# network.net
KiCad netlist of a schematic drawn in Altium Designer
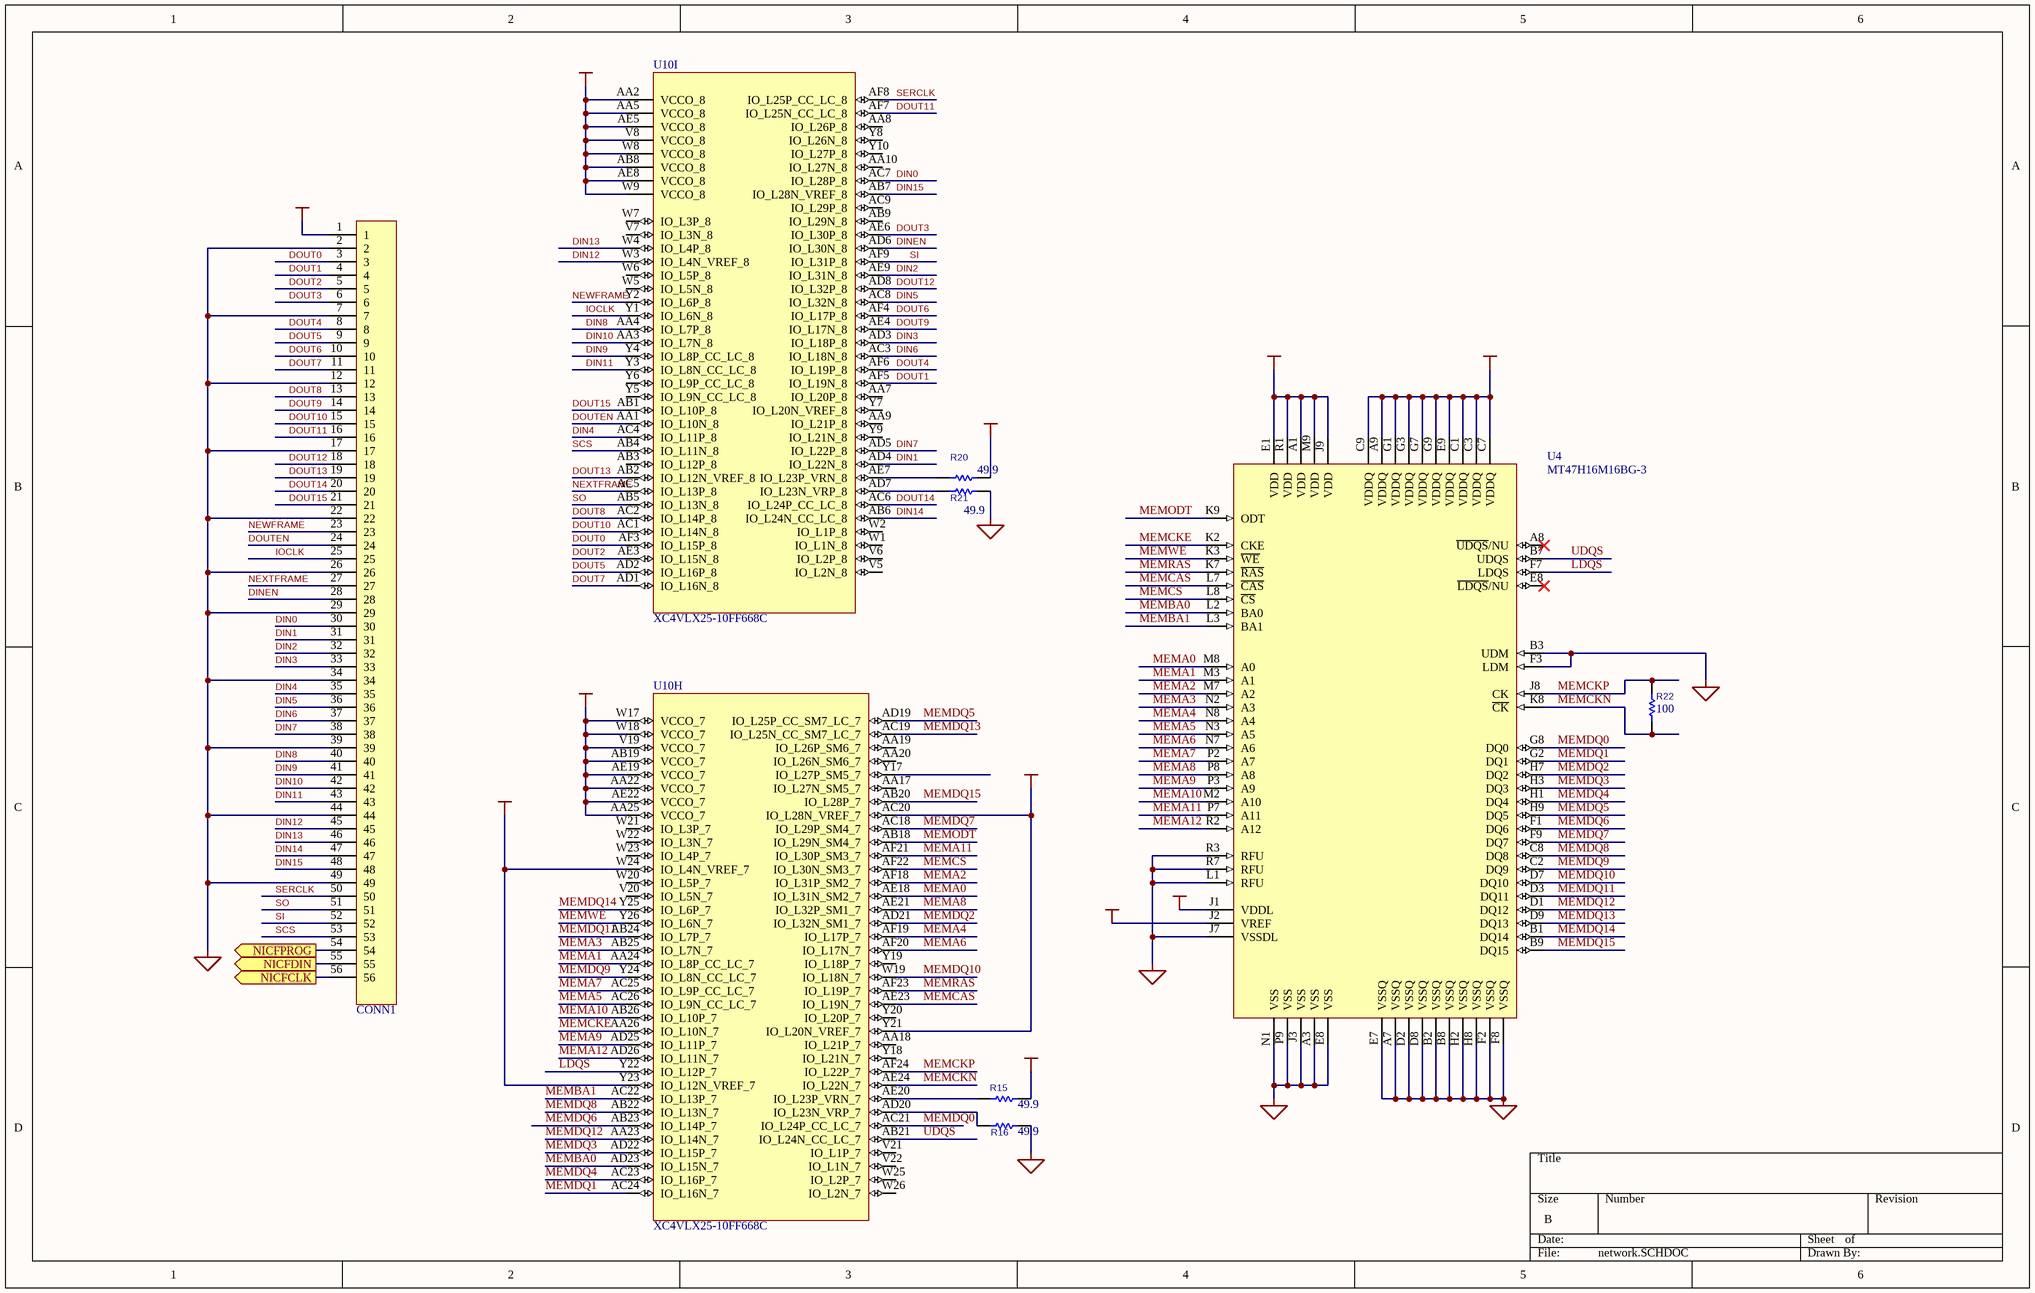
[diagram p0: network.SCHDOC]

(export (version "E")
  (design (tool "Eeschema 10.0.6"))
  (components
    (comp (ref "CONN1") (value "CON56B") (footprint "HDR56") (libsource (lib "parts") (part "CON56B")))
    (comp (ref "R15")
      (value "49.9")
      (footprint "0402")
      (description "Standard Passive Resistor")
      (fields (field (name "TOLERANCE") "1%") (field (name "Comment") "50"))
      (libsource (lib "parts") (part "RESISTOR"))
    )
    (comp (ref "R16")
      (value "49.9")
      (footprint "0402")
      (description "Standard Passive Resistor")
      (fields (field (name "TOLERANCE") "1%") (field (name "Comment") "50"))
      (libsource (lib "parts") (part "RESISTOR"))
    )
    (comp (ref "R20")
      (value "49.9")
      (footprint "0402")
      (description "Standard Passive Resistor")
      (fields (field (name "TOLERANCE") "1%") (field (name "Comment") "50"))
      (libsource (lib "parts") (part "RESISTOR"))
    )
    (comp (ref "R21")
      (value "49.9")
      (footprint "0402")
      (description "Standard Passive Resistor")
      (fields (field (name "TOLERANCE") "1%") (field (name "Comment") "50"))
      (libsource (lib "parts") (part "RESISTOR"))
    )
    (comp (ref "R22")
      (value "100")
      (footprint "0402")
      (description "Standard Passive Resistor")
      (fields (field (name "TOLERANCE") "1%") (field (name "Comment") "50"))
      (libsource (lib "parts") (part "RESISTOR"))
    )
    (comp (ref "U4")
      (value "MT47H16M16BG-3")
      (footprint "MICRON84FBGA")
      (description "Micron DDR2 SDRAM")
      (libsource (lib "parts") (part "MT47H16M16BG-3"))
    )
    (comp (ref "U10")
      (value "XC4VLX25-10FF668C")
      (footprint "Xilinx FF668")
      (description "Xilinx Virtex-4")
      (libsource (lib "parts") (part "XC4VLX25-10FF668C"))
    )
  )
  (nets
    (net (code "1") (name "+0.9VCC") (class "Default")
      (node (ref "U10") (pin "AC20") (pinfunction "IO_L28N_VREF_7_AC20") (pintype "bidirectional"))
      (node (ref "U10") (pin "W24") (pinfunction "IO_L4N_VREF_7_W24") (pintype "bidirectional"))
      (node (ref "U10") (pin "Y21") (pinfunction "IO_L20N_VREF_7_Y21") (pintype "bidirectional"))
      (node (ref "U10") (pin "Y23") (pinfunction "IO_L12N_VREF_7_Y23") (pintype "bidirectional"))
      (node (ref "U4") (pin "J2") (pinfunction "VREF_J2") (pintype "power_in"))
    )
    (net (code "2") (name "+1.8VCC") (class "Default")
      (node (ref "R15") (pin "1") (pintype "passive"))
      (node (ref "U10") (pin "AA22") (pinfunction "VCCO_7_AA22") (pintype "bidirectional"))
      (node (ref "U10") (pin "AA25") (pinfunction "VCCO_7_AA25") (pintype "bidirectional"))
      (node (ref "U10") (pin "AB19") (pinfunction "VCCO_7_AB19") (pintype "bidirectional"))
      (node (ref "U10") (pin "AE19") (pinfunction "VCCO_7_AE19") (pintype "bidirectional"))
      (node (ref "U10") (pin "AE22") (pinfunction "VCCO_7_AE22") (pintype "bidirectional"))
      (node (ref "U10") (pin "V19") (pinfunction "VCCO_7_V19") (pintype "bidirectional"))
      (node (ref "U10") (pin "W17") (pinfunction "VCCO_7_W17") (pintype "bidirectional"))
      (node (ref "U10") (pin "W18") (pinfunction "VCCO_7_W18") (pintype "bidirectional"))
      (node (ref "U4") (pin "A1") (pinfunction "VDD_A1") (pintype "power_in"))
      (node (ref "U4") (pin "A9") (pinfunction "VDDQ_A9") (pintype "power_in"))
      (node (ref "U4") (pin "C1") (pinfunction "VDDQ_C1") (pintype "power_in"))
      (node (ref "U4") (pin "C3") (pinfunction "VDDQ_C3") (pintype "power_in"))
      (node (ref "U4") (pin "C7") (pinfunction "VDDQ_C7") (pintype "power_in"))
      (node (ref "U4") (pin "C9") (pinfunction "VDDQ_C9") (pintype "power_in"))
      (node (ref "U4") (pin "E1") (pinfunction "VDD_E1") (pintype "power_in"))
      (node (ref "U4") (pin "E9") (pinfunction "VDDQ_E9") (pintype "power_in"))
      (node (ref "U4") (pin "G1") (pinfunction "VDDQ_G1") (pintype "power_in"))
      (node (ref "U4") (pin "G3") (pinfunction "VDDQ_G3") (pintype "power_in"))
      (node (ref "U4") (pin "G7") (pinfunction "VDDQ_G7") (pintype "power_in"))
      (node (ref "U4") (pin "G9") (pinfunction "VDDQ_G9") (pintype "power_in"))
      (node (ref "U4") (pin "J1") (pinfunction "VDDL_J1") (pintype "power_in"))
      (node (ref "U4") (pin "J9") (pinfunction "VDD_J9") (pintype "power_in"))
      (node (ref "U4") (pin "M9") (pinfunction "VDD_M9") (pintype "power_in"))
      (node (ref "U4") (pin "R1") (pinfunction "VDD_R1") (pintype "power_in"))
    )
    (net (code "3") (name "/DIN0") (class "Default")
      (node (ref "CONN1") (pin "30") (pinfunction "30_30") (pintype "passive"))
      (node (ref "U10") (pin "AC7") (pinfunction "IO_L28P_8_AC7") (pintype "bidirectional"))
    )
    (net (code "4") (name "/DIN1") (class "Default")
      (node (ref "CONN1") (pin "31") (pinfunction "31_31") (pintype "passive"))
      (node (ref "U10") (pin "AD4") (pinfunction "IO_L22N_8_AD4") (pintype "bidirectional"))
    )
    (net (code "5") (name "/DIN2") (class "Default")
      (node (ref "CONN1") (pin "32") (pinfunction "32_32") (pintype "passive"))
      (node (ref "U10") (pin "AE9") (pinfunction "IO_L31N_8_AE9") (pintype "bidirectional"))
    )
    (net (code "6") (name "/DIN3") (class "Default")
      (node (ref "CONN1") (pin "33") (pinfunction "33_33") (pintype "passive"))
      (node (ref "U10") (pin "AD3") (pinfunction "IO_L18P_8_AD3") (pintype "bidirectional"))
    )
    (net (code "7") (name "/DIN4") (class "Default")
      (node (ref "CONN1") (pin "35") (pinfunction "35_35") (pintype "passive"))
      (node (ref "U10") (pin "AC4") (pinfunction "IO_L11P_8_AC4") (pintype "bidirectional"))
    )
    (net (code "8") (name "/DIN5") (class "Default")
      (node (ref "CONN1") (pin "36") (pinfunction "36_36") (pintype "passive"))
      (node (ref "U10") (pin "AC8") (pinfunction "IO_L32N_8_AC8") (pintype "bidirectional"))
    )
    (net (code "9") (name "/DIN6") (class "Default")
      (node (ref "CONN1") (pin "37") (pinfunction "37_37") (pintype "passive"))
      (node (ref "U10") (pin "AC3") (pinfunction "IO_L18N_8_AC3") (pintype "bidirectional"))
    )
    (net (code "10") (name "/DIN7") (class "Default")
      (node (ref "CONN1") (pin "38") (pinfunction "38_38") (pintype "passive"))
      (node (ref "U10") (pin "AD5") (pinfunction "IO_L22P_8_AD5") (pintype "bidirectional"))
    )
    (net (code "11") (name "/DIN8") (class "Default")
      (node (ref "CONN1") (pin "40") (pinfunction "40_40") (pintype "passive"))
      (node (ref "U10") (pin "AA4") (pinfunction "IO_L7P_8_AA4") (pintype "bidirectional"))
    )
    (net (code "12") (name "/DIN9") (class "Default")
      (node (ref "CONN1") (pin "41") (pinfunction "41_41") (pintype "passive"))
      (node (ref "U10") (pin "Y4") (pinfunction "IO_L8P_CC_LC_8_Y4") (pintype "bidirectional"))
    )
    (net (code "13") (name "/DIN10") (class "Default")
      (node (ref "CONN1") (pin "42") (pinfunction "42_42") (pintype "passive"))
      (node (ref "U10") (pin "AA3") (pinfunction "IO_L7N_8_AA3") (pintype "bidirectional"))
    )
    (net (code "14") (name "/DIN11") (class "Default")
      (node (ref "CONN1") (pin "43") (pinfunction "43_43") (pintype "passive"))
      (node (ref "U10") (pin "Y3") (pinfunction "IO_L8N_CC_LC_8_Y3") (pintype "bidirectional"))
    )
    (net (code "15") (name "/DIN12") (class "Default")
      (node (ref "CONN1") (pin "45") (pinfunction "45_45") (pintype "passive"))
      (node (ref "U10") (pin "W3") (pinfunction "IO_L4N_VREF_8_W3") (pintype "bidirectional"))
    )
    (net (code "16") (name "/DIN13") (class "Default")
      (node (ref "CONN1") (pin "46") (pinfunction "46_46") (pintype "passive"))
      (node (ref "U10") (pin "W4") (pinfunction "IO_L4P_8_W4") (pintype "bidirectional"))
    )
    (net (code "17") (name "/DIN14") (class "Default")
      (node (ref "CONN1") (pin "47") (pinfunction "47_47") (pintype "passive"))
      (node (ref "U10") (pin "AB6") (pinfunction "IO_L24N_CC_LC_8_AB6") (pintype "bidirectional"))
    )
    (net (code "18") (name "/DIN15") (class "Default")
      (node (ref "CONN1") (pin "48") (pinfunction "48_48") (pintype "passive"))
      (node (ref "U10") (pin "AB7") (pinfunction "IO_L28N_VREF_8_AB7") (pintype "bidirectional"))
    )
    (net (code "19") (name "/DINEN") (class "Default")
      (node (ref "CONN1") (pin "28") (pinfunction "28_28") (pintype "passive"))
      (node (ref "U10") (pin "AD6") (pinfunction "IO_L30N_8_AD6") (pintype "bidirectional"))
    )
    (net (code "20") (name "/DOUT0") (class "Default")
      (node (ref "CONN1") (pin "3") (pinfunction "3_3") (pintype "passive"))
      (node (ref "U10") (pin "AF3") (pinfunction "IO_L15P_8_AF3") (pintype "bidirectional"))
    )
    (net (code "21") (name "/DOUT1") (class "Default")
      (node (ref "CONN1") (pin "4") (pinfunction "4_4") (pintype "passive"))
      (node (ref "U10") (pin "AF5") (pinfunction "IO_L19N_8_AF5") (pintype "bidirectional"))
    )
    (net (code "22") (name "/DOUT2") (class "Default")
      (node (ref "CONN1") (pin "5") (pinfunction "5_5") (pintype "passive"))
      (node (ref "U10") (pin "AE3") (pinfunction "IO_L15N_8_AE3") (pintype "bidirectional"))
    )
    (net (code "23") (name "/DOUT3") (class "Default")
      (node (ref "CONN1") (pin "6") (pinfunction "6_6") (pintype "passive"))
      (node (ref "U10") (pin "AE6") (pinfunction "IO_L30P_8_AE6") (pintype "bidirectional"))
    )
    (net (code "24") (name "/DOUT4") (class "Default")
      (node (ref "CONN1") (pin "8") (pinfunction "8_8") (pintype "passive"))
      (node (ref "U10") (pin "AF6") (pinfunction "IO_L19P_8_AF6") (pintype "bidirectional"))
    )
    (net (code "25") (name "/DOUT5") (class "Default")
      (node (ref "CONN1") (pin "9") (pinfunction "9_9") (pintype "passive"))
      (node (ref "U10") (pin "AD2") (pinfunction "IO_L16P_8_AD2") (pintype "bidirectional"))
    )
    (net (code "26") (name "/DOUT6") (class "Default")
      (node (ref "CONN1") (pin "10") (pinfunction "10_10") (pintype "passive"))
      (node (ref "U10") (pin "AF4") (pinfunction "IO_L17P_8_AF4") (pintype "bidirectional"))
    )
    (net (code "27") (name "/DOUT7") (class "Default")
      (node (ref "CONN1") (pin "11") (pinfunction "11_11") (pintype "passive"))
      (node (ref "U10") (pin "AD1") (pinfunction "IO_L16N_8_AD1") (pintype "bidirectional"))
    )
    (net (code "28") (name "/DOUT8") (class "Default")
      (node (ref "CONN1") (pin "13") (pinfunction "13_13") (pintype "passive"))
      (node (ref "U10") (pin "AC2") (pinfunction "IO_L14P_8_AC2") (pintype "bidirectional"))
    )
    (net (code "29") (name "/DOUT9") (class "Default")
      (node (ref "CONN1") (pin "14") (pinfunction "14_14") (pintype "passive"))
      (node (ref "U10") (pin "AE4") (pinfunction "IO_L17N_8_AE4") (pintype "bidirectional"))
    )
    (net (code "30") (name "/DOUT10") (class "Default")
      (node (ref "CONN1") (pin "15") (pinfunction "15_15") (pintype "passive"))
      (node (ref "U10") (pin "AC1") (pinfunction "IO_L14N_8_AC1") (pintype "bidirectional"))
    )
    (net (code "31") (name "/DOUT11") (class "Default")
      (node (ref "CONN1") (pin "16") (pinfunction "16_16") (pintype "passive"))
      (node (ref "U10") (pin "AF7") (pinfunction "IO_L25N_CC_LC_8_AF7") (pintype "bidirectional"))
    )
    (net (code "32") (name "/DOUT12") (class "Default")
      (node (ref "CONN1") (pin "18") (pinfunction "18_18") (pintype "passive"))
      (node (ref "U10") (pin "AD8") (pinfunction "IO_L32P_8_AD8") (pintype "bidirectional"))
    )
    (net (code "33") (name "/DOUT13") (class "Default")
      (node (ref "CONN1") (pin "19") (pinfunction "19_19") (pintype "passive"))
      (node (ref "U10") (pin "AB2") (pinfunction "IO_L12N_VREF_8_AB2") (pintype "bidirectional"))
    )
    (net (code "34") (name "/DOUT14") (class "Default")
      (node (ref "CONN1") (pin "20") (pinfunction "20_20") (pintype "passive"))
      (node (ref "U10") (pin "AC6") (pinfunction "IO_L24P_CC_LC_8_AC6") (pintype "bidirectional"))
    )
    (net (code "35") (name "/DOUT15") (class "Default")
      (node (ref "CONN1") (pin "21") (pinfunction "21_21") (pintype "passive"))
      (node (ref "U10") (pin "AB1") (pinfunction "IO_L10P_8_AB1") (pintype "bidirectional"))
    )
    (net (code "36") (name "/DOUTEN") (class "Default")
      (node (ref "CONN1") (pin "24") (pinfunction "24_24") (pintype "passive"))
      (node (ref "U10") (pin "AA1") (pinfunction "IO_L10N_8_AA1") (pintype "bidirectional"))
    )
    (net (code "37") (name "/IOCLK") (class "Default")
      (node (ref "CONN1") (pin "25") (pinfunction "25_25") (pintype "passive"))
      (node (ref "U10") (pin "Y1") (pinfunction "IO_L6N_8_Y1") (pintype "bidirectional"))
    )
    (net (code "38") (name "/LDQS") (class "Default")
      (node (ref "U10") (pin "Y22") (pinfunction "IO_L12P_7_Y22") (pintype "bidirectional"))
      (node (ref "U4") (pin "F7") (pinfunction "LDQS_F7") (pintype "bidirectional"))
    )
    (net (code "39") (name "/MEMA0") (class "Default")
      (node (ref "U10") (pin "AE18") (pinfunction "IO_L31N_SM2_7_AE18") (pintype "bidirectional"))
      (node (ref "U4") (pin "M8") (pinfunction "A0_M8") (pintype "input"))
    )
    (net (code "40") (name "/MEMA1") (class "Default")
      (node (ref "U10") (pin "AA24") (pinfunction "IO_L8P_CC_LC_7_AA24") (pintype "bidirectional"))
      (node (ref "U4") (pin "M3") (pinfunction "A1_M3") (pintype "input"))
    )
    (net (code "41") (name "/MEMA2") (class "Default")
      (node (ref "U10") (pin "AF18") (pinfunction "IO_L31P_SM2_7_AF18") (pintype "bidirectional"))
      (node (ref "U4") (pin "M7") (pinfunction "A2_M7") (pintype "input"))
    )
    (net (code "42") (name "/MEMA3") (class "Default")
      (node (ref "U10") (pin "AB25") (pinfunction "IO_L7N_7_AB25") (pintype "bidirectional"))
      (node (ref "U4") (pin "N2") (pinfunction "A3_N2") (pintype "input"))
    )
    (net (code "43") (name "/MEMA4") (class "Default")
      (node (ref "U10") (pin "AF19") (pinfunction "IO_L17P_7_AF19") (pintype "bidirectional"))
      (node (ref "U4") (pin "N8") (pinfunction "A4_N8") (pintype "input"))
    )
    (net (code "44") (name "/MEMA5") (class "Default")
      (node (ref "U10") (pin "AC26") (pinfunction "IO_L9N_CC_LC_7_AC26") (pintype "bidirectional"))
      (node (ref "U4") (pin "N3") (pinfunction "A5_N3") (pintype "input"))
    )
    (net (code "45") (name "/MEMA6") (class "Default")
      (node (ref "U10") (pin "AF20") (pinfunction "IO_L17N_7_AF20") (pintype "bidirectional"))
      (node (ref "U4") (pin "N7") (pinfunction "A6_N7") (pintype "input"))
    )
    (net (code "46") (name "/MEMA7") (class "Default")
      (node (ref "U10") (pin "AC25") (pinfunction "IO_L9P_CC_LC_7_AC25") (pintype "bidirectional"))
      (node (ref "U4") (pin "P2") (pinfunction "A7_P2") (pintype "input"))
    )
    (net (code "47") (name "/MEMA8") (class "Default")
      (node (ref "U10") (pin "AE21") (pinfunction "IO_L32P_SM1_7_AE21") (pintype "bidirectional"))
      (node (ref "U4") (pin "P8") (pinfunction "A8_P8") (pintype "input"))
    )
    (net (code "48") (name "/MEMA9") (class "Default")
      (node (ref "U10") (pin "AD25") (pinfunction "IO_L11P_7_AD25") (pintype "bidirectional"))
      (node (ref "U4") (pin "P3") (pinfunction "A9_P3") (pintype "input"))
    )
    (net (code "49") (name "/MEMA10") (class "Default")
      (node (ref "U10") (pin "AB26") (pinfunction "IO_L10P_7_AB26") (pintype "bidirectional"))
      (node (ref "U4") (pin "M2") (pinfunction "A10_M2") (pintype "input"))
    )
    (net (code "50") (name "/MEMA11") (class "Default")
      (node (ref "U10") (pin "AF21") (pinfunction "IO_L30P_SM3_7_AF21") (pintype "bidirectional"))
      (node (ref "U4") (pin "P7") (pinfunction "A11_P7") (pintype "input"))
    )
    (net (code "51") (name "/MEMA12") (class "Default")
      (node (ref "U10") (pin "AD26") (pinfunction "IO_L11N_7_AD26") (pintype "bidirectional"))
      (node (ref "U4") (pin "R2") (pinfunction "A12_R2") (pintype "input"))
    )
    (net (code "52") (name "/MEMBA0") (class "Default")
      (node (ref "U10") (pin "AD23") (pinfunction "IO_L15N_7_AD23") (pintype "bidirectional"))
      (node (ref "U4") (pin "L2") (pinfunction "BA0_L2") (pintype "input"))
    )
    (net (code "53") (name "/MEMBA1") (class "Default")
      (node (ref "U10") (pin "AC22") (pinfunction "IO_L13P_7_AC22") (pintype "bidirectional"))
      (node (ref "U4") (pin "L3") (pinfunction "BA1_L3") (pintype "input"))
    )
    (net (code "54") (name "/MEMCKE") (class "Default")
      (node (ref "U10") (pin "AA26") (pinfunction "IO_L10N_7_AA26") (pintype "bidirectional"))
      (node (ref "U4") (pin "K2") (pinfunction "CKE_K2") (pintype "input"))
    )
    (net (code "55") (name "/MEMCKN") (class "Default")
      (node (ref "R22") (pin "2") (pintype "passive"))
      (node (ref "U10") (pin "AE24") (pinfunction "IO_L22N_7_AE24") (pintype "bidirectional"))
      (node (ref "U4") (pin "K8") (pinfunction "~{CK}_K8") (pintype "input"))
    )
    (net (code "56") (name "/MEMCKP") (class "Default")
      (node (ref "R22") (pin "1") (pintype "passive"))
      (node (ref "U10") (pin "AF24") (pinfunction "IO_L22P_7_AF24") (pintype "bidirectional"))
      (node (ref "U4") (pin "J8") (pinfunction "CK_J8") (pintype "input"))
    )
    (net (code "57") (name "/MEMDQ0") (class "Default")
      (node (ref "U10") (pin "AC21") (pinfunction "IO_L24P_CC_LC_7_AC21") (pintype "bidirectional"))
      (node (ref "U4") (pin "G8") (pinfunction "DQ0_G8") (pintype "bidirectional"))
    )
    (net (code "58") (name "/MEMDQ1") (class "Default")
      (node (ref "U10") (pin "AC24") (pinfunction "IO_L16N_7_AC24") (pintype "bidirectional"))
      (node (ref "U4") (pin "G2") (pinfunction "DQ1_G2") (pintype "bidirectional"))
    )
    (net (code "59") (name "/MEMDQ2") (class "Default")
      (node (ref "U10") (pin "AD21") (pinfunction "IO_L32N_SM1_7_AD21") (pintype "bidirectional"))
      (node (ref "U4") (pin "H7") (pinfunction "DQ2_H7") (pintype "bidirectional"))
    )
    (net (code "60") (name "/MEMDQ3") (class "Default")
      (node (ref "U10") (pin "AD22") (pinfunction "IO_L15P_7_AD22") (pintype "bidirectional"))
      (node (ref "U4") (pin "H3") (pinfunction "DQ3_H3") (pintype "bidirectional"))
    )
    (net (code "61") (name "/MEMDQ4") (class "Default")
      (node (ref "U10") (pin "AC23") (pinfunction "IO_L16P_7_AC23") (pintype "bidirectional"))
      (node (ref "U4") (pin "H1") (pinfunction "DQ4_H1") (pintype "bidirectional"))
    )
    (net (code "62") (name "/MEMDQ5") (class "Default")
      (node (ref "U10") (pin "AD19") (pinfunction "IO_L25P_CC_SM7_LC_7_AD19") (pintype "bidirectional"))
      (node (ref "U4") (pin "H9") (pinfunction "DQ5_H9") (pintype "bidirectional"))
    )
    (net (code "63") (name "/MEMDQ6") (class "Default")
      (node (ref "U10") (pin "AB23") (pinfunction "IO_L14P_7_AB23") (pintype "bidirectional"))
      (node (ref "U4") (pin "F1") (pinfunction "DQ6_F1") (pintype "bidirectional"))
    )
    (net (code "64") (name "/MEMDQ7") (class "Default")
      (node (ref "U10") (pin "AC18") (pinfunction "IO_L29P_SM4_7_AC18") (pintype "bidirectional"))
      (node (ref "U4") (pin "F9") (pinfunction "DQ7_F9") (pintype "bidirectional"))
    )
    (net (code "65") (name "/MEMDQ8") (class "Default")
      (node (ref "U10") (pin "AB22") (pinfunction "IO_L13N_7_AB22") (pintype "bidirectional"))
      (node (ref "U4") (pin "C8") (pinfunction "DQ8_C8") (pintype "bidirectional"))
    )
    (net (code "66") (name "/MEMDQ9") (class "Default")
      (node (ref "U10") (pin "Y24") (pinfunction "IO_L8N_CC_LC_7_Y24") (pintype "bidirectional"))
      (node (ref "U4") (pin "C2") (pinfunction "DQ9_C2") (pintype "bidirectional"))
    )
    (net (code "67") (name "/MEMDQ10") (class "Default")
      (node (ref "U10") (pin "W19") (pinfunction "IO_L18N_7_W19") (pintype "bidirectional"))
      (node (ref "U4") (pin "D7") (pinfunction "DQ10_D7") (pintype "bidirectional"))
    )
    (net (code "68") (name "/MEMDQ11") (class "Default")
      (node (ref "U10") (pin "AB24") (pinfunction "IO_L7P_7_AB24") (pintype "bidirectional"))
      (node (ref "U4") (pin "D3") (pinfunction "DQ11_D3") (pintype "bidirectional"))
    )
    (net (code "69") (name "/MEMDQ12") (class "Default")
      (node (ref "U10") (pin "AA23") (pinfunction "IO_L14N_7_AA23") (pintype "bidirectional"))
      (node (ref "U4") (pin "D1") (pinfunction "DQ12_D1") (pintype "bidirectional"))
    )
    (net (code "70") (name "/MEMDQ13") (class "Default")
      (node (ref "U10") (pin "AC19") (pinfunction "IO_L25N_CC_SM7_LC_7_AC19") (pintype "bidirectional"))
      (node (ref "U4") (pin "D9") (pinfunction "DQ13_D9") (pintype "bidirectional"))
    )
    (net (code "71") (name "/MEMDQ14") (class "Default")
      (node (ref "U10") (pin "Y25") (pinfunction "IO_L6P_7_Y25") (pintype "bidirectional"))
      (node (ref "U4") (pin "B1") (pinfunction "DQ14_B1") (pintype "bidirectional"))
    )
    (net (code "72") (name "/MEMDQ15") (class "Default")
      (node (ref "U10") (pin "AB20") (pinfunction "IO_L28P_7_AB20") (pintype "bidirectional"))
      (node (ref "U4") (pin "B9") (pinfunction "DQ15_B9") (pintype "bidirectional"))
    )
    (net (code "73") (name "/MEMODT") (class "Default")
      (node (ref "U10") (pin "AB18") (pinfunction "IO_L29N_SM4_7_AB18") (pintype "bidirectional"))
      (node (ref "U4") (pin "K9") (pinfunction "ODT_K9") (pintype "input"))
    )
    (net (code "74") (name "/MEM~{CAS}") (class "Default")
      (node (ref "U10") (pin "AE23") (pinfunction "IO_L19N_7_AE23") (pintype "bidirectional"))
      (node (ref "U4") (pin "L7") (pinfunction "~{CAS}_L7") (pintype "input"))
    )
    (net (code "75") (name "/MEM~{CS}") (class "Default")
      (node (ref "U10") (pin "AF22") (pinfunction "IO_L30N_SM3_7_AF22") (pintype "bidirectional"))
      (node (ref "U4") (pin "L8") (pinfunction "~{CS}_L8") (pintype "input"))
    )
    (net (code "76") (name "/MEM~{RAS}") (class "Default")
      (node (ref "U10") (pin "AF23") (pinfunction "IO_L19P_7_AF23") (pintype "bidirectional"))
      (node (ref "U4") (pin "K7") (pinfunction "~{RAS}_K7") (pintype "input"))
    )
    (net (code "77") (name "/MEM~{WE}") (class "Default")
      (node (ref "U10") (pin "Y26") (pinfunction "IO_L6N_7_Y26") (pintype "bidirectional"))
      (node (ref "U4") (pin "K3") (pinfunction "~{WE}_K3") (pintype "input"))
    )
    (net (code "78") (name "/NEWFRAME") (class "Default")
      (node (ref "CONN1") (pin "23") (pinfunction "23_23") (pintype "passive"))
      (node (ref "U10") (pin "Y2") (pinfunction "IO_L6P_8_Y2") (pintype "bidirectional"))
    )
    (net (code "79") (name "/NEXTFRAME") (class "Default")
      (node (ref "CONN1") (pin "27") (pinfunction "27_27") (pintype "passive"))
      (node (ref "U10") (pin "AC5") (pinfunction "IO_L13P_8_AC5") (pintype "bidirectional"))
    )
    (net (code "80") (name "/NICFCLK") (class "Default")
      (node (ref "CONN1") (pin "56") (pinfunction "56_56") (pintype "passive"))
    )
    (net (code "81") (name "/NICFDIN") (class "Default")
      (node (ref "CONN1") (pin "55") (pinfunction "55_55") (pintype "passive"))
    )
    (net (code "82") (name "/NICFPROG") (class "Default")
      (node (ref "CONN1") (pin "54") (pinfunction "54_54") (pintype "passive"))
    )
    (net (code "83") (name "/SCS") (class "Default")
      (node (ref "CONN1") (pin "53") (pinfunction "53_53") (pintype "passive"))
      (node (ref "U10") (pin "AB4") (pinfunction "IO_L11N_8_AB4") (pintype "bidirectional"))
    )
    (net (code "84") (name "/SERCLK") (class "Default")
      (node (ref "CONN1") (pin "50") (pinfunction "50_50") (pintype "passive"))
      (node (ref "U10") (pin "AF8") (pinfunction "IO_L25P_CC_LC_8_AF8") (pintype "bidirectional"))
    )
    (net (code "85") (name "/SI") (class "Default")
      (node (ref "CONN1") (pin "52") (pinfunction "52_52") (pintype "passive"))
      (node (ref "U10") (pin "AF9") (pinfunction "IO_L31P_8_AF9") (pintype "bidirectional"))
    )
    (net (code "86") (name "/SO") (class "Default")
      (node (ref "CONN1") (pin "51") (pinfunction "51_51") (pintype "passive"))
      (node (ref "U10") (pin "AB5") (pinfunction "IO_L13N_8_AB5") (pintype "bidirectional"))
    )
    (net (code "87") (name "/UDQS") (class "Default")
      (node (ref "U10") (pin "AB21") (pinfunction "IO_L24N_CC_LC_7_AB21") (pintype "bidirectional"))
      (node (ref "U4") (pin "B7") (pinfunction "UDQS_B7") (pintype "bidirectional"))
    )
    (net (code "88") (name "3.3VCC") (class "Default") (node (ref "R20") (pin "1") (pintype "passive")))
    (net (code "89") (name "GND") (class "Default")
      (node (ref "CONN1") (pin "12") (pinfunction "12_12") (pintype "passive"))
      (node (ref "CONN1") (pin "17") (pinfunction "17_17") (pintype "passive"))
      (node (ref "CONN1") (pin "2") (pinfunction "2_2") (pintype "passive"))
      (node (ref "CONN1") (pin "22") (pinfunction "22_22") (pintype "passive"))
      (node (ref "CONN1") (pin "26") (pinfunction "26_26") (pintype "passive"))
      (node (ref "CONN1") (pin "29") (pinfunction "29_29") (pintype "passive"))
      (node (ref "CONN1") (pin "34") (pinfunction "34_34") (pintype "passive"))
      (node (ref "CONN1") (pin "39") (pinfunction "39_39") (pintype "passive"))
      (node (ref "CONN1") (pin "44") (pinfunction "44_44") (pintype "passive"))
      (node (ref "CONN1") (pin "49") (pinfunction "49_49") (pintype "passive"))
      (node (ref "CONN1") (pin "7") (pinfunction "7_7") (pintype "passive"))
      (node (ref "R16") (pin "1") (pintype "passive"))
      (node (ref "R21") (pin "1") (pintype "passive"))
      (node (ref "U4") (pin "A3") (pinfunction "VSS_A3") (pintype "power_in"))
      (node (ref "U4") (pin "A7") (pinfunction "VSSQ_A7") (pintype "power_in"))
      (node (ref "U4") (pin "B2") (pinfunction "VSSQ_B2") (pintype "power_in"))
      (node (ref "U4") (pin "B3") (pinfunction "UDM_B3") (pintype "input"))
      (node (ref "U4") (pin "B8") (pinfunction "VSSQ_B8") (pintype "power_in"))
      (node (ref "U4") (pin "D2") (pinfunction "VSSQ_D2") (pintype "power_in"))
      (node (ref "U4") (pin "D8") (pinfunction "VSSQ_D8") (pintype "power_in"))
      (node (ref "U4") (pin "E7") (pinfunction "VSSQ_E7") (pintype "power_in"))
      (node (ref "U4") (pin "E8") (pinfunction "VSS_E8") (pintype "power_in"))
      (node (ref "U4") (pin "F2") (pinfunction "VSSQ_F2") (pintype "power_in"))
      (node (ref "U4") (pin "F3") (pinfunction "LDM_F3") (pintype "input"))
      (node (ref "U4") (pin "F8") (pinfunction "VSSQ_F8") (pintype "power_in"))
      (node (ref "U4") (pin "H2") (pinfunction "VSSQ_H2") (pintype "power_in"))
      (node (ref "U4") (pin "H8") (pinfunction "VSSQ_H8") (pintype "power_in"))
      (node (ref "U4") (pin "J3") (pinfunction "VSS_J3") (pintype "power_in"))
      (node (ref "U4") (pin "J7") (pinfunction "VSSDL_J7") (pintype "power_in"))
      (node (ref "U4") (pin "L1") (pinfunction "RFU_L1") (pintype "input"))
      (node (ref "U4") (pin "N1") (pinfunction "VSS_N1") (pintype "power_in"))
      (node (ref "U4") (pin "P9") (pinfunction "VSS_P9") (pintype "power_in"))
      (node (ref "U4") (pin "R3") (pinfunction "RFU_R3") (pintype "input"))
      (node (ref "U4") (pin "R7") (pinfunction "RFU_R7") (pintype "input"))
    )
    (net (code "90") (name "Net-(U10H-IO_L23N_VRP_7)") (class "Default")
      (node (ref "R16") (pin "2") (pintype "passive"))
      (node (ref "U10") (pin "AD20") (pinfunction "IO_L23N_VRP_7_AD20") (pintype "bidirectional"))
    )
    (net (code "91") (name "Net-(U10H-IO_L23P_VRN_7)") (class "Default")
      (node (ref "R15") (pin "2") (pintype "passive"))
      (node (ref "U10") (pin "AE20") (pinfunction "IO_L23P_VRN_7_AE20") (pintype "bidirectional"))
    )
    (net (code "92") (name "Net-(U10I-IO_L23N_VRP_8)") (class "Default")
      (node (ref "R21") (pin "2") (pintype "passive"))
      (node (ref "U10") (pin "AD7") (pinfunction "IO_L23N_VRP_8_AD7") (pintype "bidirectional"))
    )
    (net (code "93") (name "Net-(U10I-IO_L23P_VRN_8)") (class "Default")
      (node (ref "R20") (pin "2") (pintype "passive"))
      (node (ref "U10") (pin "AE7") (pinfunction "IO_L23P_VRN_8_AE7") (pintype "bidirectional"))
    )
    (net (code "94") (name "VCC") (class "Default")
      (node (ref "CONN1") (pin "1") (pinfunction "1_1") (pintype "passive"))
      (node (ref "U10") (pin "AA2") (pinfunction "VCCO_8_AA2") (pintype "power_in"))
      (node (ref "U10") (pin "AA5") (pinfunction "VCCO_8_AA5") (pintype "power_in"))
      (node (ref "U10") (pin "AB8") (pinfunction "VCCO_8_AB8") (pintype "power_in"))
      (node (ref "U10") (pin "AE5") (pinfunction "VCCO_8_AE5") (pintype "power_in"))
      (node (ref "U10") (pin "AE8") (pinfunction "VCCO_8_AE8") (pintype "power_in"))
      (node (ref "U10") (pin "V8") (pinfunction "VCCO_8_V8") (pintype "power_in"))
      (node (ref "U10") (pin "W8") (pinfunction "VCCO_8_W8") (pintype "power_in"))
      (node (ref "U10") (pin "W9") (pinfunction "VCCO_8_W9") (pintype "power_in"))
    )
    (net (code "95") (name "unconnected-(U4-~{LDQS}{slash}NU-PadE8)") (class "Default")
      (node (ref "U4") (pin "E8") (pinfunction "~{LDQS}/NU_E8") (pintype "bidirectional+no_connect"))
    )
    (net (code "96") (name "unconnected-(U4-~{UDQS}{slash}NU-PadA8)") (class "Default")
      (node (ref "U4") (pin "A8") (pinfunction "~{UDQS}/NU_A8") (pintype "bidirectional+no_connect"))
    )
    (net (code "97") (name "unconnected-(U10H-IO_L1N_7-PadV22)") (class "Default")
      (node (ref "U10") (pin "V22") (pinfunction "IO_L1N_7_V22") (pintype "bidirectional"))
    )
    (net (code "98") (name "unconnected-(U10H-IO_L1P_7-PadV21)") (class "Default")
      (node (ref "U10") (pin "V21") (pinfunction "IO_L1P_7_V21") (pintype "bidirectional"))
    )
    (net (code "99") (name "unconnected-(U10H-IO_L2N_7-PadW26)") (class "Default")
      (node (ref "U10") (pin "W26") (pinfunction "IO_L2N_7_W26") (pintype "bidirectional"))
    )
    (net (code "100") (name "unconnected-(U10H-IO_L2P_7-PadW25)") (class "Default")
      (node (ref "U10") (pin "W25") (pinfunction "IO_L2P_7_W25") (pintype "bidirectional"))
    )
    (net (code "101") (name "unconnected-(U10H-IO_L3N_7-PadW22)") (class "Default")
      (node (ref "U10") (pin "W22") (pinfunction "IO_L3N_7_W22") (pintype "bidirectional"))
    )
    (net (code "102") (name "unconnected-(U10H-IO_L3P_7-PadW21)") (class "Default")
      (node (ref "U10") (pin "W21") (pinfunction "IO_L3P_7_W21") (pintype "bidirectional"))
    )
    (net (code "103") (name "unconnected-(U10H-IO_L4P_7-PadW23)") (class "Default")
      (node (ref "U10") (pin "W23") (pinfunction "IO_L4P_7_W23") (pintype "bidirectional"))
    )
    (net (code "104") (name "unconnected-(U10H-IO_L5N_7-PadV20)") (class "Default")
      (node (ref "U10") (pin "V20") (pinfunction "IO_L5N_7_V20") (pintype "bidirectional"))
    )
    (net (code "105") (name "unconnected-(U10H-IO_L5P_7-PadW20)") (class "Default")
      (node (ref "U10") (pin "W20") (pinfunction "IO_L5P_7_W20") (pintype "bidirectional"))
    )
    (net (code "106") (name "unconnected-(U10H-IO_L18P_7-PadY19)") (class "Default")
      (node (ref "U10") (pin "Y19") (pinfunction "IO_L18P_7_Y19") (pintype "bidirectional"))
    )
    (net (code "107") (name "unconnected-(U10H-IO_L20P_7-PadY20)") (class "Default")
      (node (ref "U10") (pin "Y20") (pinfunction "IO_L20P_7_Y20") (pintype "bidirectional"))
    )
    (net (code "108") (name "unconnected-(U10H-IO_L21N_7-PadY18)") (class "Default")
      (node (ref "U10") (pin "Y18") (pinfunction "IO_L21N_7_Y18") (pintype "bidirectional"))
    )
    (net (code "109") (name "unconnected-(U10H-IO_L21P_7-PadAA18)") (class "Default")
      (node (ref "U10") (pin "AA18") (pinfunction "IO_L21P_7_AA18") (pintype "bidirectional"))
    )
    (net (code "110") (name "unconnected-(U10H-IO_L26N_SM6_7-PadAA20)") (class "Default")
      (node (ref "U10") (pin "AA20") (pinfunction "IO_L26N_SM6_7_AA20") (pintype "bidirectional"))
    )
    (net (code "111") (name "unconnected-(U10H-IO_L26P_SM6_7-PadAA19)") (class "Default")
      (node (ref "U10") (pin "AA19") (pinfunction "IO_L26P_SM6_7_AA19") (pintype "bidirectional"))
    )
    (net (code "112") (name "unconnected-(U10H-IO_L27N_SM5_7-PadAA17)") (class "Default")
      (node (ref "U10") (pin "AA17") (pinfunction "IO_L27N_SM5_7_AA17") (pintype "bidirectional"))
    )
    (net (code "113") (name "unconnected-(U10H-IO_L27P_SM5_7-PadY17)") (class "Default")
      (node (ref "U10") (pin "Y17") (pinfunction "IO_L27P_SM5_7_Y17") (pintype "bidirectional"))
    )
    (net (code "114") (name "unconnected-(U10I-IO_L1N_8-PadW1)") (class "Default")
      (node (ref "U10") (pin "W1") (pinfunction "IO_L1N_8_W1") (pintype "bidirectional"))
    )
    (net (code "115") (name "unconnected-(U10I-IO_L1P_8-PadW2)") (class "Default")
      (node (ref "U10") (pin "W2") (pinfunction "IO_L1P_8_W2") (pintype "bidirectional"))
    )
    (net (code "116") (name "unconnected-(U10I-IO_L2N_8-PadV5)") (class "Default")
      (node (ref "U10") (pin "V5") (pinfunction "IO_L2N_8_V5") (pintype "bidirectional"))
    )
    (net (code "117") (name "unconnected-(U10I-IO_L2P_8-PadV6)") (class "Default")
      (node (ref "U10") (pin "V6") (pinfunction "IO_L2P_8_V6") (pintype "bidirectional"))
    )
    (net (code "118") (name "unconnected-(U10I-IO_L3N_8-PadV7)") (class "Default")
      (node (ref "U10") (pin "V7") (pinfunction "IO_L3N_8_V7") (pintype "bidirectional"))
    )
    (net (code "119") (name "unconnected-(U10I-IO_L3P_8-PadW7)") (class "Default")
      (node (ref "U10") (pin "W7") (pinfunction "IO_L3P_8_W7") (pintype "bidirectional"))
    )
    (net (code "120") (name "unconnected-(U10I-IO_L5N_8-PadW5)") (class "Default")
      (node (ref "U10") (pin "W5") (pinfunction "IO_L5N_8_W5") (pintype "bidirectional"))
    )
    (net (code "121") (name "unconnected-(U10I-IO_L5P_8-PadW6)") (class "Default")
      (node (ref "U10") (pin "W6") (pinfunction "IO_L5P_8_W6") (pintype "bidirectional"))
    )
    (net (code "122") (name "unconnected-(U10I-IO_L9N_CC_LC_8-PadY5)") (class "Default")
      (node (ref "U10") (pin "Y5") (pinfunction "IO_L9N_CC_LC_8_Y5") (pintype "bidirectional"))
    )
    (net (code "123") (name "unconnected-(U10I-IO_L9P_CC_LC_8-PadY6)") (class "Default")
      (node (ref "U10") (pin "Y6") (pinfunction "IO_L9P_CC_LC_8_Y6") (pintype "bidirectional"))
    )
    (net (code "124") (name "unconnected-(U10I-IO_L12P_8-PadAB3)") (class "Default")
      (node (ref "U10") (pin "AB3") (pinfunction "IO_L12P_8_AB3") (pintype "bidirectional"))
    )
    (net (code "125") (name "unconnected-(U10I-IO_L20N_VREF_8-PadY7)") (class "Default")
      (node (ref "U10") (pin "Y7") (pinfunction "IO_L20N_VREF_8_Y7") (pintype "bidirectional"))
    )
    (net (code "126") (name "unconnected-(U10I-IO_L20P_8-PadAA7)") (class "Default")
      (node (ref "U10") (pin "AA7") (pinfunction "IO_L20P_8_AA7") (pintype "bidirectional"))
    )
    (net (code "127") (name "unconnected-(U10I-IO_L21N_8-PadY9)") (class "Default")
      (node (ref "U10") (pin "Y9") (pinfunction "IO_L21N_8_Y9") (pintype "bidirectional"))
    )
    (net (code "128") (name "unconnected-(U10I-IO_L21P_8-PadAA9)") (class "Default")
      (node (ref "U10") (pin "AA9") (pinfunction "IO_L21P_8_AA9") (pintype "bidirectional"))
    )
    (net (code "129") (name "unconnected-(U10I-IO_L26N_8-PadY8)") (class "Default")
      (node (ref "U10") (pin "Y8") (pinfunction "IO_L26N_8_Y8") (pintype "bidirectional"))
    )
    (net (code "130") (name "unconnected-(U10I-IO_L26P_8-PadAA8)") (class "Default")
      (node (ref "U10") (pin "AA8") (pinfunction "IO_L26P_8_AA8") (pintype "bidirectional"))
    )
    (net (code "131") (name "unconnected-(U10I-IO_L27N_8-PadAA10)") (class "Default")
      (node (ref "U10") (pin "AA10") (pinfunction "IO_L27N_8_AA10") (pintype "bidirectional"))
    )
    (net (code "132") (name "unconnected-(U10I-IO_L27P_8-PadY10)") (class "Default")
      (node (ref "U10") (pin "Y10") (pinfunction "IO_L27P_8_Y10") (pintype "bidirectional"))
    )
    (net (code "133") (name "unconnected-(U10I-IO_L29N_8-PadAB9)") (class "Default")
      (node (ref "U10") (pin "AB9") (pinfunction "IO_L29N_8_AB9") (pintype "bidirectional"))
    )
    (net (code "134") (name "unconnected-(U10I-IO_L29P_8-PadAC9)") (class "Default")
      (node (ref "U10") (pin "AC9") (pinfunction "IO_L29P_8_AC9") (pintype "bidirectional"))
    )
  )
)
